# 03_-_SCHEMATIC.net
KiCad netlist of a schematic drawn in Altium Designer
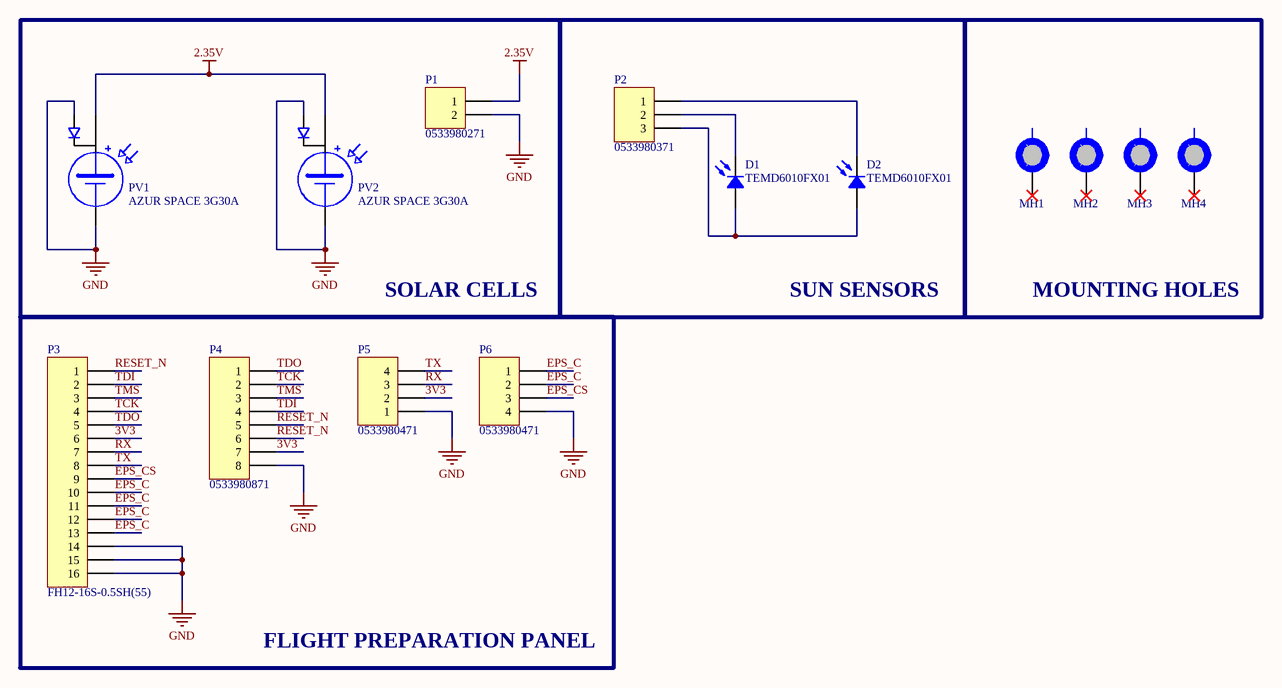
[diagram p0: [03] - SCHEMATIC.SchDoc]

(export (version "E")
  (design (tool "Eeschema 10.0.6"))
  (components
    (comp (ref "D1")
      (value "TEMD6010FX01")
      (footprint "TEMD6010FX01")
      (description "Ambient Light Sensor")
      (fields (field (name "MANUFACTURER") "Vishay Semiconductors"))
      (libsource (lib "UVG") (part "TEMD6010FX01"))
    )
    (comp (ref "D2")
      (value "TEMD6010FX01")
      (footprint "TEMD6010FX01")
      (description "Ambient Light Sensor")
      (fields (field (name "MANUFACTURER") "Vishay Semiconductors"))
      (libsource (lib "UVG") (part "TEMD6010FX01"))
    )
    (comp (ref "MH1")
      (value "MH_3.8MMNC_2.5MMD")
      (footprint "MH_3.8MMNC_2MMD_NON_COPPER_NPTH")
      (description "Mounting Hole 3.8mm Diameter (Non Copper), 2.5mm Drill NPTH")
      (libsource (lib "UVG") (part "MH_3.8MMNC_2MMD"))
    )
    (comp (ref "MH2")
      (value "MH_3.8MMNC_2.5MMD")
      (footprint "MH_3.8MMNC_2MMD_NON_COPPER_NPTH")
      (description "Mounting Hole 3.8mm Diameter (Non Copper), 2.5mm Drill NPTH")
      (libsource (lib "UVG") (part "MH_3.8MMNC_2MMD"))
    )
    (comp (ref "MH3")
      (value "MH_3.8MMNC_2.5MMD")
      (footprint "MH_3.8MMNC_2MMD_NON_COPPER_NPTH")
      (description "Mounting Hole 3.8mm Diameter (Non Copper), 2.5mm Drill NPTH")
      (libsource (lib "UVG") (part "MH_3.8MMNC_2MMD"))
    )
    (comp (ref "MH4")
      (value "MH_3.8MMNC_2.5MMD")
      (footprint "MH_3.8MMNC_2MMD_NON_COPPER_NPTH")
      (description "Mounting Hole 3.8mm Diameter (Non Copper), 2.5mm Drill NPTH")
      (libsource (lib "UVG") (part "MH_3.8MMNC_2MMD"))
    )
    (comp (ref "P1")
      (value "0533980271")
      (footprint "0533980271")
      (description "2 Positions Header, Shrouded Connector 0.049\" (1.25mm) Surface Mount, Vertical Tin")
      (fields (field (name "MANUFACTURER") "Molex"))
      (libsource (lib "UVG") (part "0533980271"))
    )
    (comp (ref "P2")
      (value "0533980371")
      (footprint "0533980371")
      (description "3 Positions Header, Shrouded Connector 0.049\" (1.25mm) Surface Mount, Vertical Tin")
      (fields (field (name "MANUFACTURER") "Molex"))
      (libsource (lib "UVG") (part "0533980371"))
    )
    (comp (ref "P3")
      (value "FH12-16S-0.5SH(55)")
      (footprint "FH12-16S-0.5SH(55)")
      (description "16 Position FFC, FPC Connector Contacts, Bottom 0.020\" (0.50mm) Surface Mount, Right Angle")
      (fields
        (field (name "MANUFACTURER") "Hirose")
        (field (name "MANUFACTURER PART NUMBER") "FH12-12S-0.5SH(55)")
      )
      (libsource (lib "UVG") (part "FH12-16S-0.5SH(55)"))
    )
    (comp (ref "P4")
      (value "0533980871")
      (footprint "0533980871")
      (description "8 Positions Header, Shrouded Connector 0.049\" (1.25mm) Surface Mount, Vertical Tin")
      (fields (field (name "MANUFACTURER") "Molex") (field (name "MANUFACTURER PART NUMBER") "53398-0871"))
      (libsource (lib "UVG") (part "0533980871"))
    )
    (comp (ref "P5")
      (value "0533980471")
      (footprint "0533980471")
      (description "4 Positions Header, Shrouded Connector 0.049\" (1.25mm) Surface Mount, Right Angle Tin")
      (fields (field (name "MANUFACTURER") "Molex") (field (name "MANUFACTURER PART NUMBER") "53398-0471"))
      (libsource (lib "UVG") (part "0533980471"))
    )
    (comp (ref "P6")
      (value "0533980471")
      (footprint "0533980471")
      (description "4 Positions Header, Shrouded Connector 0.049\" (1.25mm) Surface Mount, Right Angle Tin")
      (fields (field (name "MANUFACTURER") "Molex") (field (name "MANUFACTURER PART NUMBER") "53398-0471"))
      (libsource (lib "") (part "0533980471_1"))
    )
    (comp (ref "PV1")
      (value "AZUR SPACE 3G30A")
      (footprint "AZUR SPACE 3G30A")
      (description "30% Triple Junction GaAs Solar Cell Assembly")
      (libsource (lib "UVG") (part "AZUR SPACE 3G30A"))
    )
    (comp (ref "PV2")
      (value "AZUR SPACE 3G30A")
      (footprint "AZUR SPACE 3G30A")
      (description "30% Triple Junction GaAs Solar Cell Assembly")
      (libsource (lib "UVG") (part "AZUR SPACE 3G30A"))
    )
  )
  (nets
    (net (code "1") (name "/3V3") (class "Default")
      (node (ref "P3") (pin "6") (pinfunction "6_6") (pintype "passive"))
      (node (ref "P4") (pin "7") (pinfunction "7_7") (pintype "passive"))
      (node (ref "P5") (pin "2") (pinfunction "2_2") (pintype "passive"))
    )
    (net (code "2") (name "/EPS_C") (class "Default")
      (node (ref "P3") (pin "10") (pinfunction "10_10") (pintype "passive"))
      (node (ref "P3") (pin "11") (pinfunction "11_11") (pintype "passive"))
      (node (ref "P3") (pin "12") (pinfunction "12_12") (pintype "passive"))
      (node (ref "P3") (pin "13") (pinfunction "13_13") (pintype "passive"))
      (node (ref "P6") (pin "1") (pinfunction "1_1") (pintype "passive"))
      (node (ref "P6") (pin "2") (pinfunction "2_2") (pintype "passive"))
    )
    (net (code "3") (name "/EPS_CS") (class "Default")
      (node (ref "P3") (pin "9") (pinfunction "9_9") (pintype "passive"))
      (node (ref "P6") (pin "3") (pinfunction "3_3") (pintype "passive"))
    )
    (net (code "4") (name "/RESET_N") (class "Default")
      (node (ref "P3") (pin "1") (pinfunction "1_1") (pintype "passive"))
      (node (ref "P4") (pin "5") (pinfunction "5_5") (pintype "passive"))
      (node (ref "P4") (pin "6") (pinfunction "6_6") (pintype "passive"))
    )
    (net (code "5") (name "/RX") (class "Default")
      (node (ref "P3") (pin "7") (pinfunction "7_7") (pintype "passive"))
      (node (ref "P5") (pin "3") (pinfunction "3_3") (pintype "passive"))
    )
    (net (code "6") (name "/TCK") (class "Default")
      (node (ref "P3") (pin "4") (pinfunction "4_4") (pintype "passive"))
      (node (ref "P4") (pin "2") (pinfunction "2_2") (pintype "passive"))
    )
    (net (code "7") (name "/TDI") (class "Default")
      (node (ref "P3") (pin "2") (pinfunction "2_2") (pintype "passive"))
      (node (ref "P4") (pin "4") (pinfunction "4_4") (pintype "passive"))
    )
    (net (code "8") (name "/TDO") (class "Default")
      (node (ref "P3") (pin "5") (pinfunction "5_5") (pintype "passive"))
      (node (ref "P4") (pin "1") (pinfunction "1_1") (pintype "passive"))
    )
    (net (code "9") (name "/TMS") (class "Default")
      (node (ref "P3") (pin "3") (pinfunction "3_3") (pintype "passive"))
      (node (ref "P4") (pin "3") (pinfunction "3_3") (pintype "passive"))
    )
    (net (code "10") (name "/TX") (class "Default")
      (node (ref "P3") (pin "8") (pinfunction "8_8") (pintype "passive"))
      (node (ref "P5") (pin "4") (pinfunction "4_4") (pintype "passive"))
    )
    (net (code "11") (name "2.35V") (class "Default")
      (node (ref "P1") (pin "1") (pinfunction "1_1") (pintype "passive"))
      (node (ref "PV1") (pin "1") (pinfunction "1_1") (pintype "passive"))
      (node (ref "PV2") (pin "1") (pinfunction "1_1") (pintype "passive"))
    )
    (net (code "12") (name "GND") (class "Default")
      (node (ref "P1") (pin "2") (pinfunction "2_2") (pintype "passive"))
      (node (ref "P3") (pin "14") (pinfunction "14_14") (pintype "passive"))
      (node (ref "P3") (pin "15") (pinfunction "15_15") (pintype "passive"))
      (node (ref "P3") (pin "16") (pinfunction "16_16") (pintype "passive"))
      (node (ref "P4") (pin "8") (pinfunction "8_8") (pintype "passive"))
      (node (ref "P5") (pin "1") (pinfunction "1_1") (pintype "passive"))
      (node (ref "P6") (pin "4") (pinfunction "4_4") (pintype "passive"))
      (node (ref "PV1") (pin "2") (pinfunction "2_2") (pintype "passive"))
      (node (ref "PV1") (pin "3") (pinfunction "3_3") (pintype "passive"))
      (node (ref "PV2") (pin "2") (pinfunction "2_2") (pintype "passive"))
      (node (ref "PV2") (pin "3") (pinfunction "3_3") (pintype "passive"))
    )
    (net (code "13") (name "Net-(D1-Pad1)") (class "Default")
      (node (ref "D1") (pin "1") (pinfunction "1_1") (pintype "passive"))
      (node (ref "D2") (pin "1") (pinfunction "1_1") (pintype "passive"))
      (node (ref "P2") (pin "3") (pinfunction "3_3") (pintype "passive"))
    )
    (net (code "14") (name "Net-(D1-Pad2)") (class "Default")
      (node (ref "D1") (pin "2") (pinfunction "2_2") (pintype "passive"))
      (node (ref "P2") (pin "2") (pinfunction "2_2") (pintype "passive"))
    )
    (net (code "15") (name "Net-(D2-Pad2)") (class "Default")
      (node (ref "D2") (pin "2") (pinfunction "2_2") (pintype "passive"))
      (node (ref "P2") (pin "1") (pinfunction "1_1") (pintype "passive"))
    )
    (net (code "16") (name "unconnected-(MH1-Pad1)") (class "Default")
      (node (ref "MH1") (pin "1") (pinfunction "1_1") (pintype "passive"))
    )
    (net (code "17") (name "unconnected-(MH2-Pad1)") (class "Default")
      (node (ref "MH2") (pin "1") (pinfunction "1_1") (pintype "passive"))
    )
    (net (code "18") (name "unconnected-(MH3-Pad1)") (class "Default")
      (node (ref "MH3") (pin "1") (pinfunction "1_1") (pintype "passive"))
    )
    (net (code "19") (name "unconnected-(MH4-Pad1)") (class "Default")
      (node (ref "MH4") (pin "1") (pinfunction "1_1") (pintype "passive"))
    )
  )
)
